# MAX30101_Qwiic_PCB.net
KiCad netlist of a schematic drawn in EAGLE
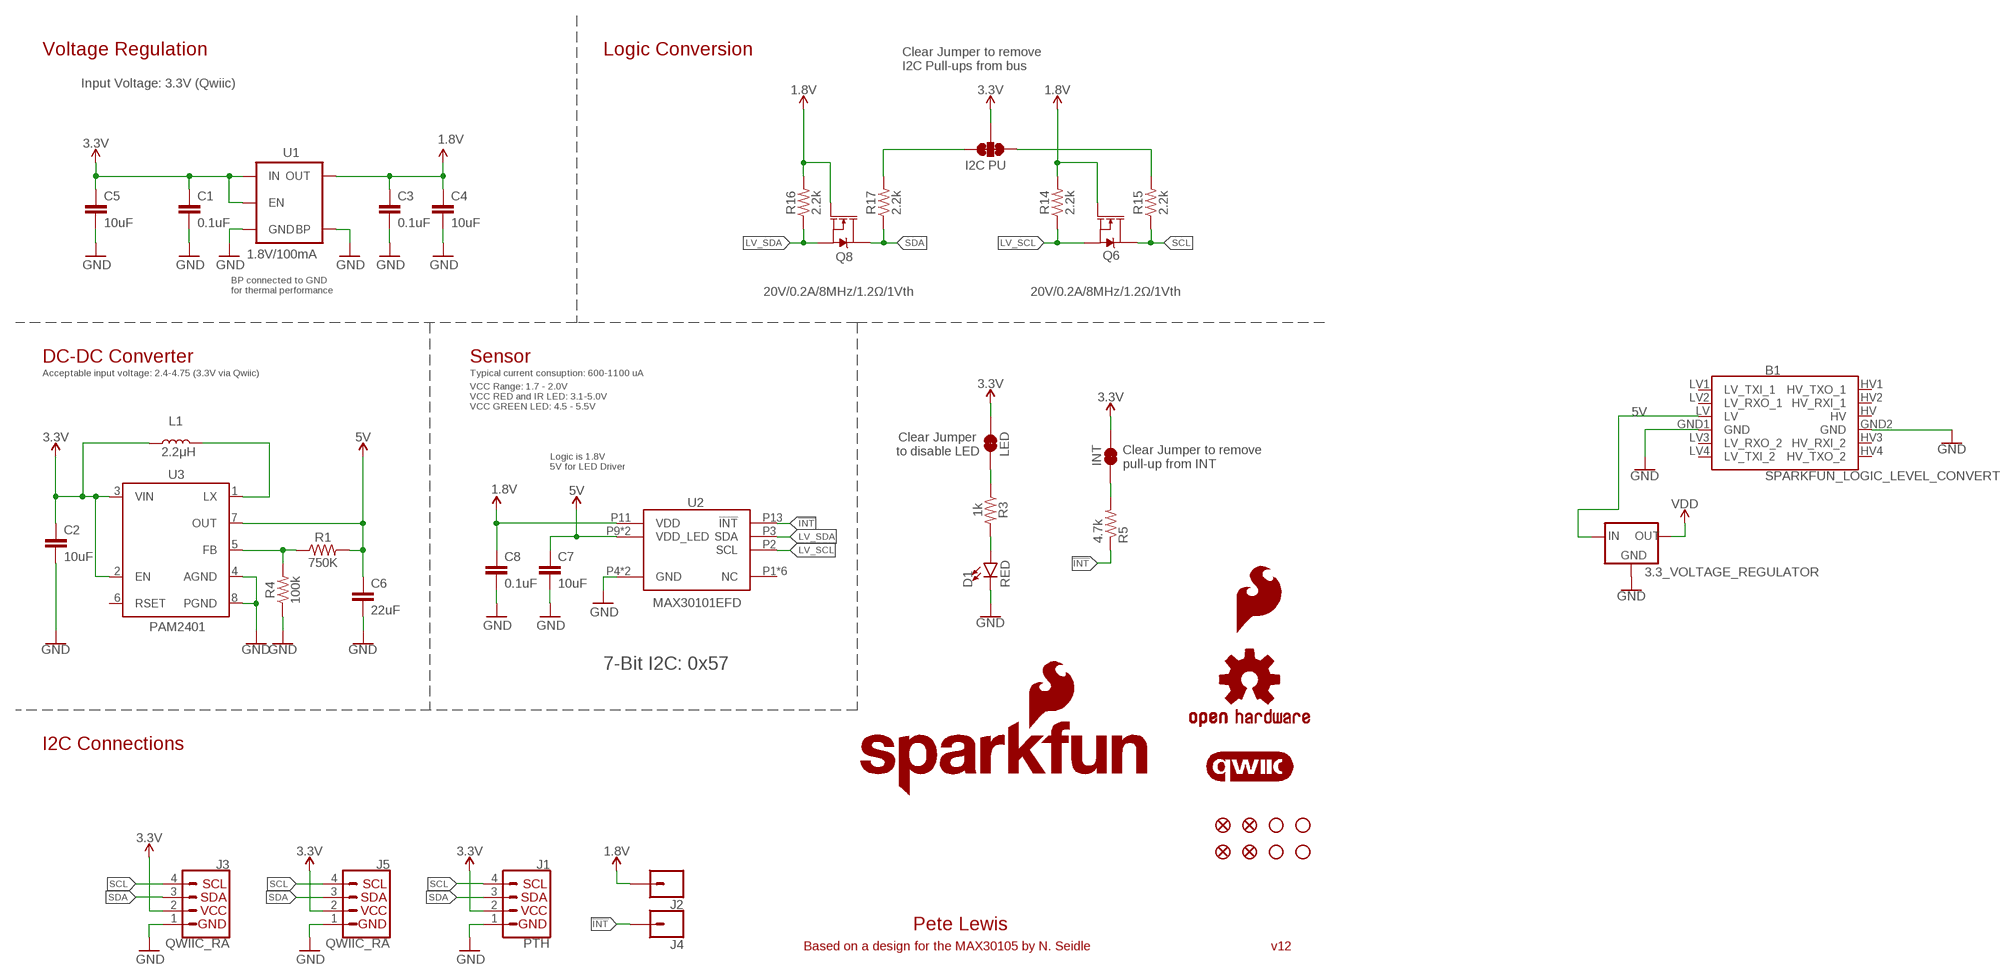
[diagram p0: schematic, sheet 1]

(export (version "E")
  (design (tool "Eeschema 10.0.6"))
  (components
    (comp (ref "3.3_VOLTAGE_REGULATOR")
      (value "V_REG_78XX-TO-220")
      (footprint "eagle-import:TO-220-ALT")
      (libsource (lib "eagle-import") (part "V_REG_78XX-TO-220"))
    )
    (comp (ref "B1")
      (value "SPARKFUN_LOGIC_LEVEL_CONVERTER")
      (footprint "eagle-import:SPARKFUN_LOGIC_LEVEL_CONVERTER")
      (libsource (lib "eagle-import") (part "SPARKFUN_LOGIC_LEVEL_CONVERTER"))
    )
    (comp (ref "C1")
      (value "0.1uF")
      (footprint "eagle-import:0402")
      (libsource (lib "eagle-import") (part "0.1UF-0402-16V-10%"))
    )
    (comp (ref "C2")
      (value "10uF")
      (footprint "eagle-import:0603")
      (libsource (lib "eagle-import") (part "10UF-0603-6.3V-20%"))
    )
    (comp (ref "C3")
      (value "0.1uF")
      (footprint "eagle-import:0402")
      (libsource (lib "eagle-import") (part "0.1UF-0402-16V-10%"))
    )
    (comp (ref "C4")
      (value "10uF")
      (footprint "eagle-import:0603")
      (libsource (lib "eagle-import") (part "10UF-0603-6.3V-20%"))
    )
    (comp (ref "C5")
      (value "10uF")
      (footprint "eagle-import:0603")
      (libsource (lib "eagle-import") (part "10UF-0603-6.3V-20%"))
    )
    (comp (ref "C6")
      (value "22uF")
      (footprint "eagle-import:0805")
      (libsource (lib "eagle-import") (part "22UF-0805-6.3V-20%"))
    )
    (comp (ref "C7")
      (value "10uF")
      (footprint "eagle-import:0603")
      (libsource (lib "eagle-import") (part "10UF-0603-6.3V-20%"))
    )
    (comp (ref "C8")
      (value "0.1uF")
      (footprint "eagle-import:0402")
      (libsource (lib "eagle-import") (part "0.1UF-0402-16V-10%"))
    )
    (comp (ref "D1")
      (value "RED")
      (footprint "eagle-import:LED-0603")
      (libsource (lib "eagle-import") (part "LED-RED0603"))
    )
    (comp (ref "FID1")
      (value "FIDUCIAL1X2")
      (footprint "eagle-import:FIDUCIAL-1X2")
      (libsource (lib "eagle-import") (part "FIDUCIAL1X2"))
    )
    (comp (ref "FID2")
      (value "FIDUCIAL1X2")
      (footprint "eagle-import:FIDUCIAL-1X2")
      (libsource (lib "eagle-import") (part "FIDUCIAL1X2"))
    )
    (comp (ref "FID3")
      (value "FIDUCIAL1X2")
      (footprint "eagle-import:FIDUCIAL-1X2")
      (libsource (lib "eagle-import") (part "FIDUCIAL1X2"))
    )
    (comp (ref "FID4")
      (value "FIDUCIAL1X2")
      (footprint "eagle-import:FIDUCIAL-1X2")
      (libsource (lib "eagle-import") (part "FIDUCIAL1X2"))
    )
    (comp (ref "J1")
      (value "PTH")
      (footprint "eagle-import:1X04_NO_SILK")
      (libsource (lib "eagle-import") (part "I2C_STANDARD_NO_SILK"))
    )
    (comp (ref "J2")
      (value "CONN_01PTH_NO_SILK_YES_STOP")
      (footprint "eagle-import:1X01_NO_SILK")
      (libsource (lib "eagle-import") (part "CONN_01PTH_NO_SILK_YES_STOP"))
    )
    (comp (ref "J3")
      (value "QWIIC_RA")
      (footprint "eagle-import:JST04_1MM_RA")
      (libsource (lib "eagle-import") (part "QWIIC_CONNECTORJS-1MM"))
    )
    (comp (ref "J4")
      (value "CONN_01PTH_NO_SILK_YES_STOP")
      (footprint "eagle-import:1X01_NO_SILK")
      (libsource (lib "eagle-import") (part "CONN_01PTH_NO_SILK_YES_STOP"))
    )
    (comp (ref "J5")
      (value "QWIIC_RA")
      (footprint "eagle-import:JST04_1MM_RA")
      (libsource (lib "eagle-import") (part "QWIIC_CONNECTORJS-1MM"))
    )
    (comp (ref "JP1")
      (value "LED")
      (footprint "eagle-import:SMT-JUMPER_2_NC_TRACE_SILK")
      (libsource (lib "eagle-import") (part "JUMPER-SMT_2_NC_TRACE_SILK"))
    )
    (comp (ref "JP2")
      (value "INT")
      (footprint "eagle-import:SMT-JUMPER_2_NC_TRACE_SILK")
      (libsource (lib "eagle-import") (part "JUMPER-SMT_2_NC_TRACE_SILK"))
    )
    (comp (ref "JP4")
      (value "I2C PU")
      (footprint "eagle-import:SMT-JUMPER_3_2-NC_TRACE_SILK")
      (libsource (lib "eagle-import") (part "JUMPER-SMT_3_2-NC_TRACE_SILK"))
    )
    (comp (ref "L1")
      (value "2.2μH")
      (footprint "eagle-import:0806")
      (libsource (lib "eagle-import") (part "2.2μH_SHIELDED_INDUCTOR"))
    )
    (comp (ref "LOGO1")
      (value "SFE_LOGO_NAME_FLAME.1_INCH")
      (footprint "eagle-import:SFE_LOGO_NAME_FLAME_.1")
      (libsource (lib "eagle-import") (part "SFE_LOGO_NAME_FLAME.1_INCH"))
    )
    (comp (ref "LOGO2")
      (value "OSHW-LOGOS")
      (footprint "eagle-import:OSHW-LOGO-S")
      (libsource (lib "eagle-import") (part "OSHW-LOGOS"))
    )
    (comp (ref "LOGO3")
      (value "QWIIC_LOGO_5MM")
      (footprint "eagle-import:QWIIC_5MM")
      (libsource (lib "eagle-import") (part "QWIIC_LOGO_5MM"))
    )
    (comp (ref "LOGO4")
      (value "SFE_LOGO_FLAME.1_INCH")
      (footprint "eagle-import:SFE_LOGO_FLAME_.1")
      (libsource (lib "eagle-import") (part "SFE_LOGO_FLAME.1_INCH"))
    )
    (comp (ref "Q6")
      (value "20V/0.2A/8MHz/1.2Ω/1Vth")
      (footprint "eagle-import:SOT-416FL")
      (libsource (lib "eagle-import") (part "MOSFET-NCH-RE1C00UNTL"))
    )
    (comp (ref "Q8")
      (value "20V/0.2A/8MHz/1.2Ω/1Vth")
      (footprint "eagle-import:SOT-416FL")
      (libsource (lib "eagle-import") (part "MOSFET-NCH-RE1C00UNTL"))
    )
    (comp (ref "R1")
      (value "750K")
      (footprint "eagle-import:0603")
      (libsource (lib "eagle-import") (part "750KOHM-0603-1/10W-1%"))
    )
    (comp (ref "R3")
      (value "1k")
      (footprint "eagle-import:0603")
      (libsource (lib "eagle-import") (part "1KOHM-0603-1/10W-1%"))
    )
    (comp (ref "R4")
      (value "100k")
      (footprint "eagle-import:0603")
      (libsource (lib "eagle-import") (part "100KOHM-0603-1/10W-1%"))
    )
    (comp (ref "R5")
      (value "4.7k")
      (footprint "eagle-import:0603")
      (libsource (lib "eagle-import") (part "4.7KOHM-0603-1/10W-1%"))
    )
    (comp (ref "R14")
      (value "2.2k")
      (footprint "eagle-import:0603")
      (libsource (lib "eagle-import") (part "2.2KOHM-0603-1/10W-1%"))
    )
    (comp (ref "R15")
      (value "2.2k")
      (footprint "eagle-import:0603")
      (libsource (lib "eagle-import") (part "2.2KOHM-0603-1/10W-1%"))
    )
    (comp (ref "R16")
      (value "2.2k")
      (footprint "eagle-import:0603")
      (libsource (lib "eagle-import") (part "2.2KOHM-0603-1/10W-1%"))
    )
    (comp (ref "R17")
      (value "2.2k")
      (footprint "eagle-import:0603")
      (libsource (lib "eagle-import") (part "2.2KOHM-0603-1/10W-1%"))
    )
    (comp (ref "STANDOFF1")
      (value "STAND-OFF")
      (footprint "eagle-import:STAND-OFF")
      (libsource (lib "eagle-import") (part "STAND-OFF"))
    )
    (comp (ref "STANDOFF2")
      (value "STAND-OFF")
      (footprint "eagle-import:STAND-OFF")
      (libsource (lib "eagle-import") (part "STAND-OFF"))
    )
    (comp (ref "STANDOFF3")
      (value "STAND-OFF")
      (footprint "eagle-import:STAND-OFF")
      (libsource (lib "eagle-import") (part "STAND-OFF"))
    )
    (comp (ref "STANDOFF4")
      (value "STAND-OFF")
      (footprint "eagle-import:STAND-OFF")
      (libsource (lib "eagle-import") (part "STAND-OFF"))
    )
    (comp (ref "U1")
      (value "1.8V/100mA")
      (footprint "eagle-import:SC70")
      (libsource (lib "eagle-import") (part "V_REG_SP62141.8V"))
    )
    (comp (ref "U2")
      (value "MAX30101EFD")
      (footprint "eagle-import:14_PIN_OESIP")
      (libsource (lib "eagle-import") (part "MAX30101EFD"))
    )
    (comp (ref "U3")
      (value "PAM2401")
      (footprint "eagle-import:MSOP8")
      (libsource (lib "eagle-import") (part "PAM2401"))
    )
  )
  (nets
    (net (code "1") (name "/HV") (class "Default")
      (node (ref "B1") (pin "HV") (pinfunction "HV_HV") (pintype "power_in"))
    )
    (net (code "2") (name "/~{INT}") (class "Default")
      (node (ref "J4") (pin "1") (pinfunction "1_1") (pintype "passive"))
      (node (ref "R5") (pin "1") (pinfunction "1_1") (pintype "passive"))
      (node (ref "U2") (pin "P13") (pinfunction "~{INT}_P13") (pintype "bidirectional"))
    )
    (net (code "3") (name "1.8V") (class "Default")
      (node (ref "C3") (pin "1") (pinfunction "1_1") (pintype "passive"))
      (node (ref "C4") (pin "1") (pinfunction "1_1") (pintype "passive"))
      (node (ref "C8") (pin "1") (pinfunction "1_1") (pintype "passive"))
      (node (ref "J2") (pin "1") (pinfunction "1_1") (pintype "passive"))
      (node (ref "Q6") (pin "1") (pinfunction "G_1") (pintype "bidirectional"))
      (node (ref "Q8") (pin "1") (pinfunction "G_1") (pintype "bidirectional"))
      (node (ref "R14") (pin "2") (pinfunction "2_2") (pintype "passive"))
      (node (ref "R16") (pin "2") (pinfunction "2_2") (pintype "passive"))
      (node (ref "U1") (pin "5") (pinfunction "OUT_5") (pintype "passive"))
      (node (ref "U2") (pin "P11") (pinfunction "VDD_P11") (pintype "power_in"))
    )
    (net (code "4") (name "3.3V") (class "Default")
      (node (ref "C1") (pin "1") (pinfunction "1_1") (pintype "passive"))
      (node (ref "C2") (pin "1") (pinfunction "1_1") (pintype "passive"))
      (node (ref "C5") (pin "1") (pinfunction "1_1") (pintype "passive"))
      (node (ref "J1") (pin "2") (pinfunction "2_2") (pintype "power_in"))
      (node (ref "J3") (pin "2") (pinfunction "2_2") (pintype "power_in"))
      (node (ref "J5") (pin "2") (pinfunction "2_2") (pintype "power_in"))
      (node (ref "JP1") (pin "2") (pinfunction "2_2") (pintype "passive"))
      (node (ref "JP2") (pin "2") (pinfunction "2_2") (pintype "passive"))
      (node (ref "JP4") (pin "2") (pinfunction "2_2") (pintype "passive"))
      (node (ref "L1") (pin "1") (pinfunction "1_1") (pintype "passive"))
      (node (ref "U1") (pin "1") (pinfunction "IN_1") (pintype "input"))
      (node (ref "U1") (pin "3") (pinfunction "EN_3") (pintype "input"))
      (node (ref "U3") (pin "2") (pinfunction "EN_2") (pintype "bidirectional"))
      (node (ref "U3") (pin "3") (pinfunction "VIN_3") (pintype "bidirectional"))
    )
    (net (code "5") (name "5V") (class "Default")
      (node (ref "C6") (pin "1") (pinfunction "1_1") (pintype "passive"))
      (node (ref "C7") (pin "1") (pinfunction "1_1") (pintype "passive"))
      (node (ref "R1") (pin "2") (pinfunction "2_2") (pintype "passive"))
      (node (ref "U2") (pin "P10") (pinfunction "VDD_LED_P10") (pintype "power_in"))
      (node (ref "U2") (pin "P9") (pinfunction "VDD_LED_P9") (pintype "power_in"))
      (node (ref "U3") (pin "7") (pinfunction "OUT_7") (pintype "bidirectional"))
    )
    (net (code "6") (name "GND") (class "Default")
      (node (ref "3.3_VOLTAGE_REGULATOR") (pin "GND") (pinfunction "GND_GND") (pintype "input"))
      (node (ref "B1") (pin "GND1") (pinfunction "GND_GND1") (pintype "power_in"))
      (node (ref "B1") (pin "GND2") (pinfunction "GND_GND2") (pintype "power_in"))
      (node (ref "C1") (pin "2") (pinfunction "2_2") (pintype "passive"))
      (node (ref "C2") (pin "2") (pinfunction "2_2") (pintype "passive"))
      (node (ref "C3") (pin "2") (pinfunction "2_2") (pintype "passive"))
      (node (ref "C4") (pin "2") (pinfunction "2_2") (pintype "passive"))
      (node (ref "C5") (pin "2") (pinfunction "2_2") (pintype "passive"))
      (node (ref "C6") (pin "2") (pinfunction "2_2") (pintype "passive"))
      (node (ref "C7") (pin "2") (pinfunction "2_2") (pintype "passive"))
      (node (ref "C8") (pin "2") (pinfunction "2_2") (pintype "passive"))
      (node (ref "D1") (pin "C") (pinfunction "C_C") (pintype "passive"))
      (node (ref "J1") (pin "1") (pinfunction "1_1") (pintype "power_in"))
      (node (ref "J3") (pin "1") (pinfunction "1_1") (pintype "power_in"))
      (node (ref "J5") (pin "1") (pinfunction "1_1") (pintype "power_in"))
      (node (ref "R4") (pin "1") (pinfunction "1_1") (pintype "passive"))
      (node (ref "U1") (pin "2") (pinfunction "GND_2") (pintype "input"))
      (node (ref "U1") (pin "4") (pinfunction "BP_4") (pintype "input"))
      (node (ref "U2") (pin "P12") (pinfunction "GND_P12") (pintype "power_in"))
      (node (ref "U2") (pin "P4") (pinfunction "GND_P4") (pintype "power_in"))
      (node (ref "U3") (pin "4") (pinfunction "AGND_4") (pintype "bidirectional"))
      (node (ref "U3") (pin "8") (pinfunction "PGND_8") (pintype "bidirectional"))
    )
    (net (code "7") (name "LV_SCL") (class "Default")
      (node (ref "Q6") (pin "2") (pinfunction "S_2") (pintype "bidirectional"))
      (node (ref "R14") (pin "1") (pinfunction "1_1") (pintype "passive"))
      (node (ref "U2") (pin "P2") (pinfunction "SCL_P2") (pintype "bidirectional"))
    )
    (net (code "8") (name "LV_SDA") (class "Default")
      (node (ref "Q8") (pin "2") (pinfunction "S_2") (pintype "bidirectional"))
      (node (ref "R16") (pin "1") (pinfunction "1_1") (pintype "passive"))
      (node (ref "U2") (pin "P3") (pinfunction "SDA_P3") (pintype "bidirectional"))
    )
    (net (code "9") (name "Net-(3.3_VOLTAGE_REGULATOR-PadIN)") (class "Default")
      (node (ref "3.3_VOLTAGE_REGULATOR") (pin "IN") (pinfunction "IN_IN") (pintype "input"))
      (node (ref "B1") (pin "LV") (pinfunction "LV_LV") (pintype "power_in"))
    )
    (net (code "10") (name "Net-(D1-PadA)") (class "Default")
      (node (ref "D1") (pin "A") (pinfunction "A_A") (pintype "passive"))
      (node (ref "R3") (pin "2") (pinfunction "2_2") (pintype "passive"))
    )
    (net (code "11") (name "Net-(JP1-Pad1)") (class "Default")
      (node (ref "JP1") (pin "1") (pinfunction "1_1") (pintype "passive"))
      (node (ref "R3") (pin "1") (pinfunction "1_1") (pintype "passive"))
    )
    (net (code "12") (name "Net-(JP2-Pad1)") (class "Default")
      (node (ref "JP2") (pin "1") (pinfunction "1_1") (pintype "passive"))
      (node (ref "R5") (pin "2") (pinfunction "2_2") (pintype "passive"))
    )
    (net (code "13") (name "Net-(JP4-Pad1)") (class "Default")
      (node (ref "JP4") (pin "1") (pinfunction "1_1") (pintype "passive"))
      (node (ref "R17") (pin "2") (pinfunction "2_2") (pintype "passive"))
    )
    (net (code "14") (name "Net-(JP4-Pad3)") (class "Default")
      (node (ref "JP4") (pin "3") (pinfunction "3_3") (pintype "passive"))
      (node (ref "R15") (pin "2") (pinfunction "2_2") (pintype "passive"))
    )
    (net (code "15") (name "Net-(U3-FB)") (class "Default")
      (node (ref "R1") (pin "1") (pinfunction "1_1") (pintype "passive"))
      (node (ref "R4") (pin "2") (pinfunction "2_2") (pintype "passive"))
      (node (ref "U3") (pin "5") (pinfunction "FB_5") (pintype "bidirectional"))
    )
    (net (code "16") (name "Net-(U3-LX)") (class "Default")
      (node (ref "L1") (pin "2") (pinfunction "2_2") (pintype "passive"))
      (node (ref "U3") (pin "1") (pinfunction "LX_1") (pintype "bidirectional"))
    )
    (net (code "17") (name "SCL") (class "Default")
      (node (ref "J1") (pin "4") (pinfunction "4_4") (pintype "passive"))
      (node (ref "J3") (pin "4") (pinfunction "4_4") (pintype "passive"))
      (node (ref "J5") (pin "4") (pinfunction "4_4") (pintype "passive"))
      (node (ref "Q6") (pin "3") (pinfunction "D_3") (pintype "bidirectional"))
      (node (ref "R15") (pin "1") (pinfunction "1_1") (pintype "passive"))
    )
    (net (code "18") (name "SDA") (class "Default")
      (node (ref "J1") (pin "3") (pinfunction "3_3") (pintype "passive"))
      (node (ref "J3") (pin "3") (pinfunction "3_3") (pintype "passive"))
      (node (ref "J5") (pin "3") (pinfunction "3_3") (pintype "passive"))
      (node (ref "Q8") (pin "3") (pinfunction "D_3") (pintype "bidirectional"))
      (node (ref "R17") (pin "1") (pinfunction "1_1") (pintype "passive"))
    )
    (net (code "19") (name "VDD") (class "Default")
      (node (ref "3.3_VOLTAGE_REGULATOR") (pin "OUT") (pinfunction "OUT_OUT") (pintype "passive"))
    )
    (net (code "20") (name "unconnected-(B1-HV_RXI_1-PadHV2)") (class "Default")
      (node (ref "B1") (pin "HV2") (pinfunction "HV_RXI_1_HV2") (pintype "bidirectional"))
    )
    (net (code "21") (name "unconnected-(B1-HV_RXI_2-PadHV3)") (class "Default")
      (node (ref "B1") (pin "HV3") (pinfunction "HV_RXI_2_HV3") (pintype "bidirectional"))
    )
    (net (code "22") (name "unconnected-(B1-HV_TXO_1-PadHV1)") (class "Default")
      (node (ref "B1") (pin "HV1") (pinfunction "HV_TXO_1_HV1") (pintype "bidirectional"))
    )
    (net (code "23") (name "unconnected-(B1-HV_TXO_2-PadHV4)") (class "Default")
      (node (ref "B1") (pin "HV4") (pinfunction "HV_TXO_2_HV4") (pintype "bidirectional"))
    )
    (net (code "24") (name "unconnected-(B1-LV_RXO_1-PadLV2)") (class "Default")
      (node (ref "B1") (pin "LV2") (pinfunction "LV_RXO_1_LV2") (pintype "bidirectional"))
    )
    (net (code "25") (name "unconnected-(B1-LV_RXO_2-PadLV3)") (class "Default")
      (node (ref "B1") (pin "LV3") (pinfunction "LV_RXO_2_LV3") (pintype "bidirectional"))
    )
    (net (code "26") (name "unconnected-(B1-LV_TXI_1-PadLV1)") (class "Default")
      (node (ref "B1") (pin "LV1") (pinfunction "LV_TXI_1_LV1") (pintype "bidirectional"))
    )
    (net (code "27") (name "unconnected-(B1-LV_TXI_2-PadLV4)") (class "Default")
      (node (ref "B1") (pin "LV4") (pinfunction "LV_TXI_2_LV4") (pintype "bidirectional"))
    )
    (net (code "28") (name "unconnected-(U2-NC-PadP1)") (class "Default")
      (node (ref "U2") (pin "P1") (pinfunction "NC_P1") (pintype "no_connect"))
    )
    (net (code "29") (name "unconnected-(U2-NC-PadP5)") (class "Default")
      (node (ref "U2") (pin "P5") (pinfunction "NC_P5") (pintype "no_connect"))
    )
    (net (code "30") (name "unconnected-(U2-NC-PadP6)") (class "Default")
      (node (ref "U2") (pin "P6") (pinfunction "NC_P6") (pintype "no_connect"))
    )
    (net (code "31") (name "unconnected-(U2-NC-PadP7)") (class "Default")
      (node (ref "U2") (pin "P7") (pinfunction "NC_P7") (pintype "no_connect"))
    )
    (net (code "32") (name "unconnected-(U2-NC-PadP8)") (class "Default")
      (node (ref "U2") (pin "P8") (pinfunction "NC_P8") (pintype "no_connect"))
    )
    (net (code "33") (name "unconnected-(U2-NC-PadP14)") (class "Default")
      (node (ref "U2") (pin "P14") (pinfunction "NC_P14") (pintype "no_connect"))
    )
    (net (code "34") (name "unconnected-(U3-RSET-Pad6)") (class "Default")
      (node (ref "U3") (pin "6") (pinfunction "RSET_6") (pintype "bidirectional"))
    )
  )
)
